# SCH_RS-485.net
KiCad netlist of a schematic drawn in Altium Designer
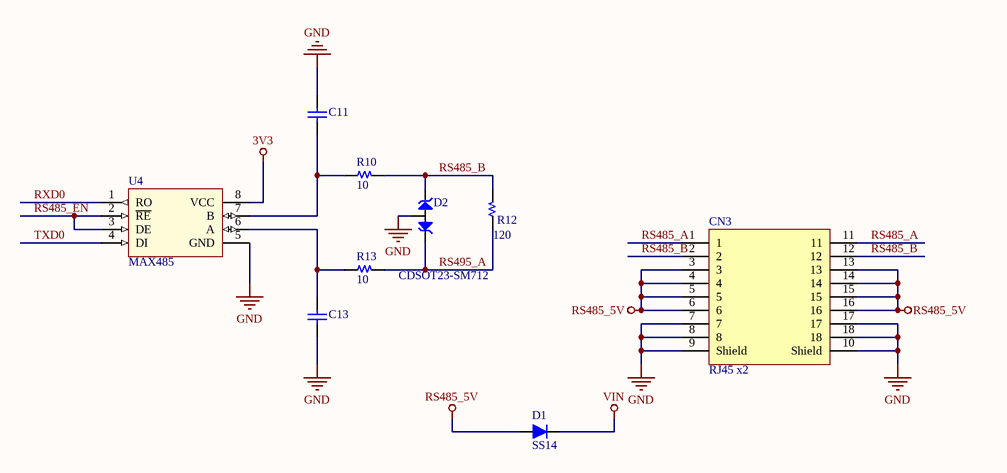
[diagram p0: SCH_RS-485.SchDoc]

(export (version "E")
  (design (tool "Eeschema 10.0.6"))
  (components
    (comp (ref "C11")
      (value "10nF")
      (footprint "C 0805")
      (description "Capacitor non-pol")
      (libsource (lib "chipfc_libs") (part "Capacitor NP"))
    )
    (comp (ref "C13")
      (value "10nF")
      (footprint "C 0805")
      (description "Capacitor non-pol")
      (libsource (lib "chipfc_libs") (part "Capacitor NP"))
    )
    (comp (ref "CN3")
      (value "RJ45 x2")
      (footprint "CONN/RJ45/x2")
      (description "Connector RJ45 X2")
      (libsource (lib "chipfc_altium_libs") (part "CON RJ45 x2"))
    )
    (comp (ref "D1")
      (value "SS14")
      (footprint "DO-214AC (SMA)")
      (description "Default Diode")
      (libsource (lib "chipfc_libs") (part "Diode"))
    )
    (comp (ref "D2")
      (value "CDSOT23-SM712")
      (footprint "SOT-23")
      (description "TVS DIODE 7V/12V 14V/26V SOT23-3")
      (libsource (lib "chipfc_libs") (part "CDSOT23-SM712"))
    )
    (comp (ref "R10")
      (value "10")
      (footprint "R 0805")
      (description "Resistor")
      (libsource (lib "chipfc_libs") (part "Resistor"))
    )
    (comp (ref "R12")
      (value "120")
      (footprint "R 0805")
      (description "Resistor")
      (libsource (lib "chipfc_libs") (part "Resistor"))
    )
    (comp (ref "R13")
      (value "10")
      (footprint "R 0805")
      (description "Resistor")
      (libsource (lib "chipfc_libs") (part "Resistor"))
    )
    (comp (ref "U4")
      (value "MAX485")
      (footprint "SOIC-8")
      (description "Low-Power, Slew-Rate-Limited  RS-485/RS-422 Transceivers")
      (libsource (lib "chipfc_altium_libs") (part "MAX485"))
    )
  )
  (nets
    (net (code "1") (name "/RS485_A") (class "Default")
      (node (ref "CN3") (pin "1") (pinfunction "1_1") (pintype "passive"))
      (node (ref "CN3") (pin "11") (pinfunction "11_11") (pintype "passive"))
    )
    (net (code "2") (name "/RS485_B") (class "Default")
      (node (ref "CN3") (pin "12") (pinfunction "12_12") (pintype "passive"))
      (node (ref "CN3") (pin "2") (pinfunction "2_2") (pintype "passive"))
      (node (ref "D2") (pin "2") (pinfunction "IO2_2") (pintype "passive"))
      (node (ref "R10") (pin "2") (pinfunction "2_2") (pintype "passive"))
      (node (ref "R12") (pin "2") (pinfunction "2_2") (pintype "passive"))
    )
    (net (code "3") (name "/RS485_EN") (class "Default")
      (node (ref "U4") (pin "2") (pinfunction "~{RE}_2") (pintype "input"))
      (node (ref "U4") (pin "3") (pinfunction "DE_3") (pintype "input"))
    )
    (net (code "4") (name "/RS495_A") (class "Default")
      (node (ref "D2") (pin "1") (pinfunction "IO1_1") (pintype "passive"))
      (node (ref "R12") (pin "1") (pinfunction "1_1") (pintype "passive"))
      (node (ref "R13") (pin "2") (pinfunction "2_2") (pintype "passive"))
    )
    (net (code "5") (name "/RXD0") (class "Default")
      (node (ref "U4") (pin "1") (pinfunction "RO_1") (pintype "output"))
    )
    (net (code "6") (name "/TXD0") (class "Default")
      (node (ref "U4") (pin "4") (pinfunction "DI_4") (pintype "input"))
    )
    (net (code "7") (name "3V3") (class "Default")
      (node (ref "U4") (pin "8") (pinfunction "VCC_8") (pintype "passive"))
    )
    (net (code "8") (name "GND") (class "Default")
      (node (ref "C11") (pin "1") (pinfunction "1_1") (pintype "passive"))
      (node (ref "C13") (pin "2") (pinfunction "2_2") (pintype "passive"))
      (node (ref "CN3") (pin "10") (pinfunction "Shield_10") (pintype "passive"))
      (node (ref "CN3") (pin "17") (pinfunction "17_17") (pintype "passive"))
      (node (ref "CN3") (pin "18") (pinfunction "18_18") (pintype "passive"))
      (node (ref "CN3") (pin "7") (pinfunction "7_7") (pintype "passive"))
      (node (ref "CN3") (pin "8") (pinfunction "8_8") (pintype "passive"))
      (node (ref "CN3") (pin "9") (pinfunction "Shield_9") (pintype "passive"))
      (node (ref "D2") (pin "3") (pinfunction "COM_3") (pintype "passive"))
      (node (ref "U4") (pin "5") (pinfunction "GND_5") (pintype "passive"))
    )
    (net (code "9") (name "Net-(U4-A)") (class "Default")
      (node (ref "C13") (pin "1") (pinfunction "1_1") (pintype "passive"))
      (node (ref "R13") (pin "1") (pinfunction "1_1") (pintype "passive"))
      (node (ref "U4") (pin "6") (pinfunction "A_6") (pintype "bidirectional"))
    )
    (net (code "10") (name "Net-(U4-B)") (class "Default")
      (node (ref "C11") (pin "2") (pinfunction "2_2") (pintype "passive"))
      (node (ref "R10") (pin "1") (pinfunction "1_1") (pintype "passive"))
      (node (ref "U4") (pin "7") (pinfunction "B_7") (pintype "bidirectional"))
    )
    (net (code "11") (name "RS485_5V") (class "Default")
      (node (ref "CN3") (pin "13") (pinfunction "13_13") (pintype "passive"))
      (node (ref "CN3") (pin "14") (pinfunction "14_14") (pintype "passive"))
      (node (ref "CN3") (pin "15") (pinfunction "15_15") (pintype "passive"))
      (node (ref "CN3") (pin "16") (pinfunction "16_16") (pintype "passive"))
      (node (ref "CN3") (pin "3") (pinfunction "3_3") (pintype "passive"))
      (node (ref "CN3") (pin "4") (pinfunction "4_4") (pintype "passive"))
      (node (ref "CN3") (pin "5") (pinfunction "5_5") (pintype "passive"))
      (node (ref "CN3") (pin "6") (pinfunction "6_6") (pintype "passive"))
      (node (ref "D1") (pin "1") (pinfunction "A_1") (pintype "passive"))
    )
    (net (code "12") (name "VIN") (class "Default")
      (node (ref "D1") (pin "2") (pinfunction "K_2") (pintype "passive"))
    )
  )
)
